# ups-node-atmega168.net
KiCad netlist of a schematic drawn in EAGLE
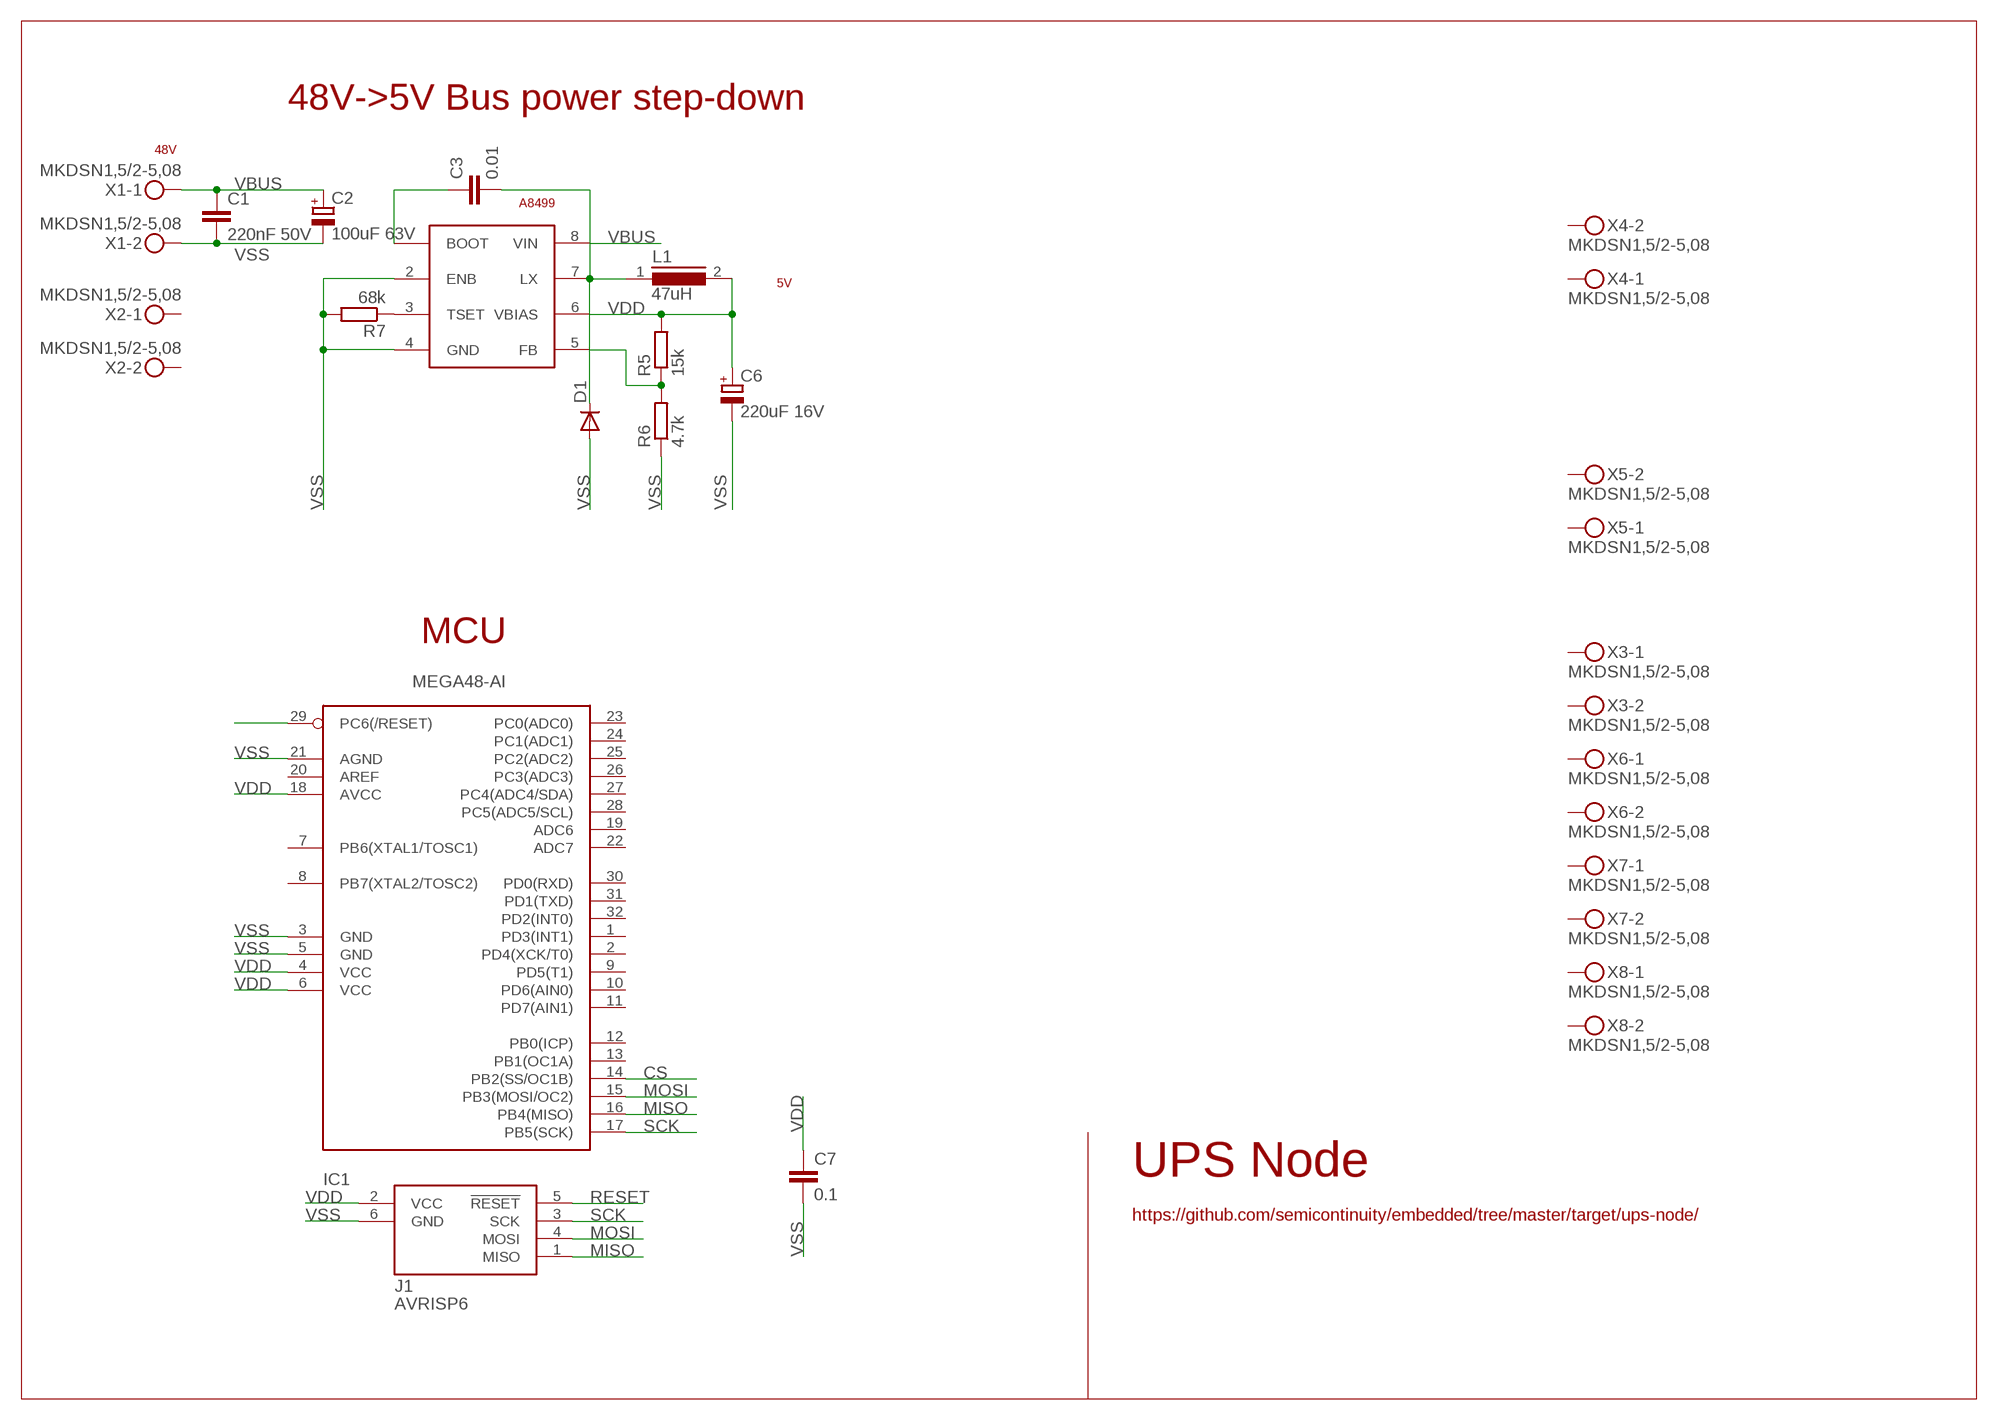
[diagram p0: schematic, sheet 1]

(export (version "E")
  (design (tool "Eeschema 10.0.6"))
  (components
    (comp (ref "C1")
      (value "220nF 50V")
      (footprint "eagle-import:C0805")
      (libsource (lib "eagle-import") (part "C-EUC0805"))
    )
    (comp (ref "C2")
      (value "100uF 63V")
      (footprint "eagle-import:153CLV-1010")
      (libsource (lib "eagle-import") (part "CPOL-EU153CLV-1010"))
    )
    (comp (ref "C3")
      (value "0.01")
      (footprint "eagle-import:C0805")
      (libsource (lib "eagle-import") (part "C-EUC0805"))
    )
    (comp (ref "C6")
      (value "220uF 16V")
      (footprint "eagle-import:153CLV-0605")
      (libsource (lib "eagle-import") (part "CPOL-EU153CLV-0605"))
    )
    (comp (ref "C7")
      (value "0.1")
      (footprint "eagle-import:C0805")
      (libsource (lib "eagle-import") (part "C-EUC0805"))
    )
    (comp (ref "D1")
      (value "DIODE-SMB")
      (footprint "eagle-import:SMB")
      (libsource (lib "eagle-import") (part "DIODE-SMB"))
    )
    (comp (ref "IC1")
      (value "MEGA48-AI")
      (footprint "eagle-import:TQFP32-08")
      (libsource (lib "eagle-import") (part "MEGA8-AI"))
    )
    (comp (ref "J1")
      (value "AVRISP6")
      (footprint "eagle-import:CON6P2R")
      (libsource (lib "eagle-import") (part "AVRISP6"))
    )
    (comp (ref "L1")
      (value "47uH")
      (footprint "eagle-import:DR127")
      (libsource (lib "eagle-import") (part "DR127"))
    )
    (comp (ref "R5")
      (value "15k")
      (footprint "eagle-import:R0805")
      (libsource (lib "eagle-import") (part "R-EU_R0805"))
    )
    (comp (ref "R6")
      (value "4.7k")
      (footprint "eagle-import:R0805")
      (libsource (lib "eagle-import") (part "R-EU_R0805"))
    )
    (comp (ref "R7")
      (value "68k")
      (footprint "eagle-import:R0805")
      (libsource (lib "eagle-import") (part "R-EU_R0805"))
    )
    (comp (ref "U$1")
      (value "A8499")
      (footprint "eagle-import:SO08")
      (libsource (lib "eagle-import") (part "A8499SLJT"))
    )
    (comp (ref "X1")
      (value "MKDSN1,5/2-5,08")
      (footprint "eagle-import:MKDSN1,5_2-5,08")
      (fields (field (name "MPN") "MKDSN 1,5/2-5.08"))
      (libsource (lib "eagle-import") (part "MKDSN1,5/2-5,08"))
    )
    (comp (ref "X2")
      (value "MKDSN1,5/2-5,08")
      (footprint "eagle-import:MKDSN1,5_2-5,08")
      (fields (field (name "MPN") "MKDSN 1,5/2-5.08"))
      (libsource (lib "eagle-import") (part "MKDSN1,5/2-5,08"))
    )
    (comp (ref "X3")
      (value "MKDSN1,5/2-5,08")
      (footprint "eagle-import:MKDSN1,5_2-5,08")
      (fields (field (name "MPN") "MKDSN 1,5/2-5.08"))
      (libsource (lib "eagle-import") (part "MKDSN1,5/2-5,08"))
    )
    (comp (ref "X4")
      (value "MKDSN1,5/2-5,08")
      (footprint "eagle-import:MKDSN1,5_2-5,08")
      (fields (field (name "MPN") "MKDSN 1,5/2-5.08"))
      (libsource (lib "eagle-import") (part "MKDSN1,5/2-5,08"))
    )
    (comp (ref "X5")
      (value "MKDSN1,5/2-5,08")
      (footprint "eagle-import:MKDSN1,5_2-5,08")
      (fields (field (name "MPN") "MKDSN 1,5/2-5.08"))
      (libsource (lib "eagle-import") (part "MKDSN1,5/2-5,08"))
    )
    (comp (ref "X6")
      (value "MKDSN1,5/2-5,08")
      (footprint "eagle-import:MKDSN1,5_2-5,08")
      (fields (field (name "MPN") "MKDSN 1,5/2-5.08"))
      (libsource (lib "eagle-import") (part "MKDSN1,5/2-5,08"))
    )
    (comp (ref "X7")
      (value "MKDSN1,5/2-5,08")
      (footprint "eagle-import:MKDSN1,5_2-5,08")
      (fields (field (name "MPN") "MKDSN 1,5/2-5.08"))
      (libsource (lib "eagle-import") (part "MKDSN1,5/2-5,08"))
    )
    (comp (ref "X8")
      (value "MKDSN1,5/2-5,08")
      (footprint "eagle-import:MKDSN1,5_2-5,08")
      (fields (field (name "MPN") "MKDSN 1,5/2-5.08"))
      (libsource (lib "eagle-import") (part "MKDSN1,5/2-5,08"))
    )
  )
  (nets
    (net (code "1") (name "/CS") (class "Default")
      (node (ref "IC1") (pin "14") (pinfunction "PB2(SS/OC1B)_14") (pintype "bidirectional"))
    )
    (net (code "2") (name "/MISO") (class "Default")
      (node (ref "IC1") (pin "16") (pinfunction "PB4(MISO)_16") (pintype "bidirectional"))
      (node (ref "J1") (pin "1") (pinfunction "MISO_1") (pintype "input"))
    )
    (net (code "3") (name "/MOSI") (class "Default")
      (node (ref "IC1") (pin "15") (pinfunction "PB3(MOSI/OC2)_15") (pintype "bidirectional"))
      (node (ref "J1") (pin "4") (pinfunction "MOSI_4") (pintype "output"))
    )
    (net (code "4") (name "/RESET") (class "Default")
      (node (ref "IC1") (pin "29") (pinfunction "PC6(/RESET)_29") (pintype "bidirectional"))
      (node (ref "J1") (pin "5") (pinfunction "~{RESET}_5") (pintype "output"))
    )
    (net (code "5") (name "/SCK") (class "Default")
      (node (ref "IC1") (pin "17") (pinfunction "PB5(SCK)_17") (pintype "bidirectional"))
      (node (ref "J1") (pin "3") (pinfunction "SCK_3") (pintype "output"))
    )
    (net (code "6") (name "/VBUS") (class "Default")
      (node (ref "C1") (pin "1") (pinfunction "1_1") (pintype "passive"))
      (node (ref "C2") (pin "+") (pinfunction "+_+") (pintype "passive"))
      (node (ref "U$1") (pin "8") (pinfunction "VIN_8") (pintype "power_in"))
      (node (ref "X1") (pin "1") (pinfunction "KL_1") (pintype "passive"))
    )
    (net (code "7") (name "/VDD") (class "Default")
      (node (ref "C6") (pin "+") (pinfunction "+_+") (pintype "passive"))
      (node (ref "C7") (pin "1") (pinfunction "1_1") (pintype "passive"))
      (node (ref "IC1") (pin "18") (pinfunction "AVCC_18") (pintype "bidirectional"))
      (node (ref "IC1") (pin "4") (pinfunction "VCC_4") (pintype "bidirectional"))
      (node (ref "IC1") (pin "6") (pinfunction "VCC_6") (pintype "bidirectional"))
      (node (ref "J1") (pin "2") (pinfunction "VCC_2") (pintype "power_in"))
      (node (ref "L1") (pin "2") (pinfunction "2_2") (pintype "passive"))
      (node (ref "R5") (pin "2") (pinfunction "2_2") (pintype "passive"))
      (node (ref "U$1") (pin "6") (pinfunction "VBIAS_6") (pintype "power_in"))
    )
    (net (code "8") (name "/VSS") (class "Default")
      (node (ref "C1") (pin "2") (pinfunction "2_2") (pintype "passive"))
      (node (ref "C2") (pin "-") (pinfunction "-_-") (pintype "passive"))
      (node (ref "C6") (pin "-") (pinfunction "-_-") (pintype "passive"))
      (node (ref "C7") (pin "2") (pinfunction "2_2") (pintype "passive"))
      (node (ref "D1") (pin "A") (pinfunction "A_A") (pintype "passive"))
      (node (ref "IC1") (pin "21") (pinfunction "AGND_21") (pintype "bidirectional"))
      (node (ref "IC1") (pin "3") (pinfunction "GND_3") (pintype "bidirectional"))
      (node (ref "IC1") (pin "5") (pinfunction "GND_5") (pintype "bidirectional"))
      (node (ref "J1") (pin "6") (pinfunction "GND_6") (pintype "power_in"))
      (node (ref "R6") (pin "1") (pinfunction "1_1") (pintype "passive"))
      (node (ref "R7") (pin "2") (pinfunction "2_2") (pintype "passive"))
      (node (ref "U$1") (pin "2") (pinfunction "ENB_2") (pintype "power_in"))
      (node (ref "U$1") (pin "4") (pinfunction "GND_4") (pintype "power_in"))
      (node (ref "X1") (pin "2") (pinfunction "KL_2") (pintype "passive"))
    )
    (net (code "9") (name "Net-(U$1-BOOT)") (class "Default")
      (node (ref "C3") (pin "1") (pinfunction "1_1") (pintype "passive"))
      (node (ref "U$1") (pin "1") (pinfunction "BOOT_1") (pintype "power_in"))
    )
    (net (code "10") (name "Net-(U$1-FB)") (class "Default")
      (node (ref "R5") (pin "1") (pinfunction "1_1") (pintype "passive"))
      (node (ref "R6") (pin "2") (pinfunction "2_2") (pintype "passive"))
      (node (ref "U$1") (pin "5") (pinfunction "FB_5") (pintype "power_in"))
    )
    (net (code "11") (name "Net-(U$1-LX)") (class "Default")
      (node (ref "C3") (pin "2") (pinfunction "2_2") (pintype "passive"))
      (node (ref "D1") (pin "C") (pinfunction "C_C") (pintype "passive"))
      (node (ref "L1") (pin "1") (pinfunction "1_1") (pintype "passive"))
      (node (ref "U$1") (pin "7") (pinfunction "LX_7") (pintype "power_in"))
    )
    (net (code "12") (name "Net-(U$1-TSET)") (class "Default")
      (node (ref "R7") (pin "1") (pinfunction "1_1") (pintype "passive"))
      (node (ref "U$1") (pin "3") (pinfunction "TSET_3") (pintype "power_in"))
    )
    (net (code "13") (name "unconnected-(IC1-ADC6-Pad19)") (class "Default")
      (node (ref "IC1") (pin "19") (pinfunction "ADC6_19") (pintype "bidirectional"))
    )
    (net (code "14") (name "unconnected-(IC1-ADC7-Pad22)") (class "Default")
      (node (ref "IC1") (pin "22") (pinfunction "ADC7_22") (pintype "bidirectional"))
    )
    (net (code "15") (name "unconnected-(IC1-AREF-Pad20)") (class "Default")
      (node (ref "IC1") (pin "20") (pinfunction "AREF_20") (pintype "bidirectional"))
    )
    (net (code "16") (name "unconnected-(IC1-PB0(ICP)-Pad12)") (class "Default")
      (node (ref "IC1") (pin "12") (pinfunction "PB0(ICP)_12") (pintype "bidirectional"))
    )
    (net (code "17") (name "unconnected-(IC1-PB1(OC1A)-Pad13)") (class "Default")
      (node (ref "IC1") (pin "13") (pinfunction "PB1(OC1A)_13") (pintype "bidirectional"))
    )
    (net (code "18") (name "unconnected-(IC1-PB6(XTAL1{slash}TOSC1)-Pad7)") (class "Default")
      (node (ref "IC1") (pin "7") (pinfunction "PB6(XTAL1/TOSC1)_7") (pintype "bidirectional"))
    )
    (net (code "19") (name "unconnected-(IC1-PB7(XTAL2{slash}TOSC2)-Pad8)") (class "Default")
      (node (ref "IC1") (pin "8") (pinfunction "PB7(XTAL2/TOSC2)_8") (pintype "bidirectional"))
    )
    (net (code "20") (name "unconnected-(IC1-PC0(ADC0)-Pad23)") (class "Default")
      (node (ref "IC1") (pin "23") (pinfunction "PC0(ADC0)_23") (pintype "bidirectional"))
    )
    (net (code "21") (name "unconnected-(IC1-PC1(ADC1)-Pad24)") (class "Default")
      (node (ref "IC1") (pin "24") (pinfunction "PC1(ADC1)_24") (pintype "bidirectional"))
    )
    (net (code "22") (name "unconnected-(IC1-PC2(ADC2)-Pad25)") (class "Default")
      (node (ref "IC1") (pin "25") (pinfunction "PC2(ADC2)_25") (pintype "bidirectional"))
    )
    (net (code "23") (name "unconnected-(IC1-PC3(ADC3)-Pad26)") (class "Default")
      (node (ref "IC1") (pin "26") (pinfunction "PC3(ADC3)_26") (pintype "bidirectional"))
    )
    (net (code "24") (name "unconnected-(IC1-PC4(ADC4{slash}SDA)-Pad27)") (class "Default")
      (node (ref "IC1") (pin "27") (pinfunction "PC4(ADC4/SDA)_27") (pintype "bidirectional"))
    )
    (net (code "25") (name "unconnected-(IC1-PC5(ADC5{slash}SCL)-Pad28)") (class "Default")
      (node (ref "IC1") (pin "28") (pinfunction "PC5(ADC5/SCL)_28") (pintype "bidirectional"))
    )
    (net (code "26") (name "unconnected-(IC1-PD0(RXD)-Pad30)") (class "Default")
      (node (ref "IC1") (pin "30") (pinfunction "PD0(RXD)_30") (pintype "bidirectional"))
    )
    (net (code "27") (name "unconnected-(IC1-PD1(TXD)-Pad31)") (class "Default")
      (node (ref "IC1") (pin "31") (pinfunction "PD1(TXD)_31") (pintype "bidirectional"))
    )
    (net (code "28") (name "unconnected-(IC1-PD2(INT0)-Pad32)") (class "Default")
      (node (ref "IC1") (pin "32") (pinfunction "PD2(INT0)_32") (pintype "bidirectional"))
    )
    (net (code "29") (name "unconnected-(IC1-PD3(INT1)-Pad1)") (class "Default")
      (node (ref "IC1") (pin "1") (pinfunction "PD3(INT1)_1") (pintype "bidirectional"))
    )
    (net (code "30") (name "unconnected-(IC1-PD4(XCK{slash}T0)-Pad2)") (class "Default")
      (node (ref "IC1") (pin "2") (pinfunction "PD4(XCK/T0)_2") (pintype "bidirectional"))
    )
    (net (code "31") (name "unconnected-(IC1-PD5(T1)-Pad9)") (class "Default")
      (node (ref "IC1") (pin "9") (pinfunction "PD5(T1)_9") (pintype "bidirectional"))
    )
    (net (code "32") (name "unconnected-(IC1-PD6(AIN0)-Pad10)") (class "Default")
      (node (ref "IC1") (pin "10") (pinfunction "PD6(AIN0)_10") (pintype "bidirectional"))
    )
    (net (code "33") (name "unconnected-(IC1-PD7(AIN1)-Pad11)") (class "Default")
      (node (ref "IC1") (pin "11") (pinfunction "PD7(AIN1)_11") (pintype "bidirectional"))
    )
    (net (code "34") (name "unconnected-(X2A-KL-Pad1)") (class "Default")
      (node (ref "X2") (pin "1") (pinfunction "KL_1") (pintype "passive"))
    )
    (net (code "35") (name "unconnected-(X2B-KL-Pad2)") (class "Default")
      (node (ref "X2") (pin "2") (pinfunction "KL_2") (pintype "passive"))
    )
    (net (code "36") (name "unconnected-(X3A-KL-Pad1)") (class "Default")
      (node (ref "X3") (pin "1") (pinfunction "KL_1") (pintype "passive"))
    )
    (net (code "37") (name "unconnected-(X3B-KL-Pad2)") (class "Default")
      (node (ref "X3") (pin "2") (pinfunction "KL_2") (pintype "passive"))
    )
    (net (code "38") (name "unconnected-(X4A-KL-Pad1)") (class "Default")
      (node (ref "X4") (pin "1") (pinfunction "KL_1") (pintype "passive"))
    )
    (net (code "39") (name "unconnected-(X4B-KL-Pad2)") (class "Default")
      (node (ref "X4") (pin "2") (pinfunction "KL_2") (pintype "passive"))
    )
    (net (code "40") (name "unconnected-(X5A-KL-Pad1)") (class "Default")
      (node (ref "X5") (pin "1") (pinfunction "KL_1") (pintype "passive"))
    )
    (net (code "41") (name "unconnected-(X5B-KL-Pad2)") (class "Default")
      (node (ref "X5") (pin "2") (pinfunction "KL_2") (pintype "passive"))
    )
    (net (code "42") (name "unconnected-(X6A-KL-Pad1)") (class "Default")
      (node (ref "X6") (pin "1") (pinfunction "KL_1") (pintype "passive"))
    )
    (net (code "43") (name "unconnected-(X6B-KL-Pad2)") (class "Default")
      (node (ref "X6") (pin "2") (pinfunction "KL_2") (pintype "passive"))
    )
    (net (code "44") (name "unconnected-(X7A-KL-Pad1)") (class "Default")
      (node (ref "X7") (pin "1") (pinfunction "KL_1") (pintype "passive"))
    )
    (net (code "45") (name "unconnected-(X7B-KL-Pad2)") (class "Default")
      (node (ref "X7") (pin "2") (pinfunction "KL_2") (pintype "passive"))
    )
    (net (code "46") (name "unconnected-(X8A-KL-Pad1)") (class "Default")
      (node (ref "X8") (pin "1") (pinfunction "KL_1") (pintype "passive"))
    )
    (net (code "47") (name "unconnected-(X8B-KL-Pad2)") (class "Default")
      (node (ref "X8") (pin "2") (pinfunction "KL_2") (pintype "passive"))
    )
  )
)
